# LEDSandButtons.net
KiCad netlist of a schematic drawn in Altium Designer
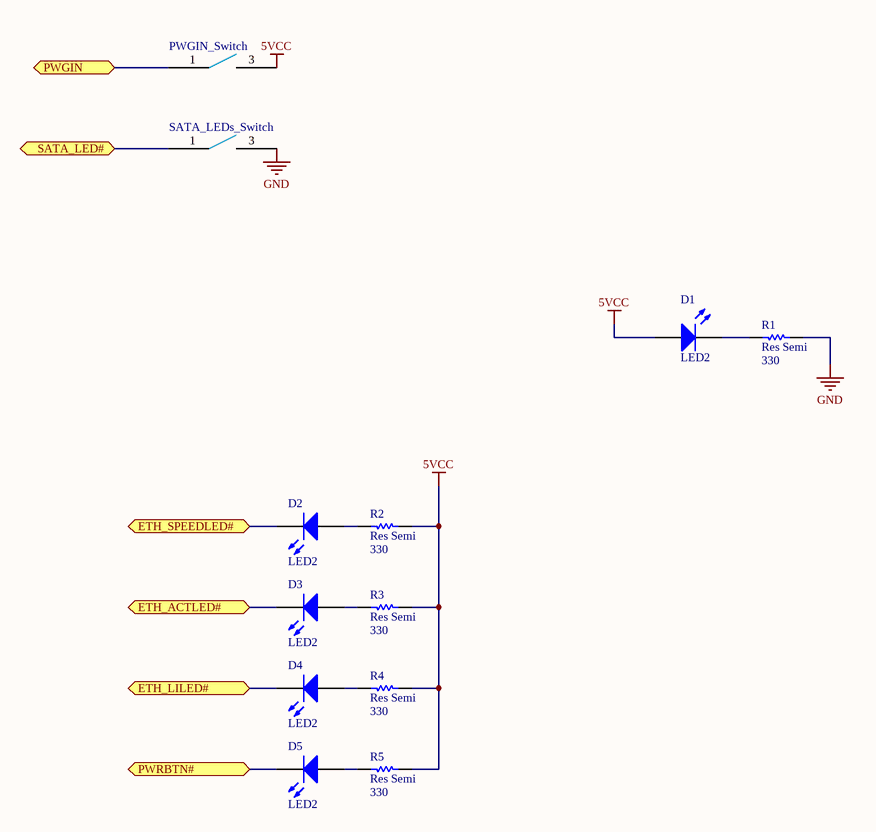
[diagram p0: LEDSandButtons.SchDoc]

(export (version "E")
  (design (tool "Eeschema 10.0.6"))
  (components
    (comp (ref "D1")
      (value "LED2")
      (footprint "C0805")
      (description "Typical RED, GREEN, YELLOW, AMBER GaAs LED")
      (fields (field (name "PUBLISHER") "Altium Limited"))
      (libsource (lib "Miscellaneous Devices") (part "LED2"))
    )
    (comp (ref "D2")
      (value "LED2")
      (footprint "C0805")
      (description "Typical RED, GREEN, YELLOW, AMBER GaAs LED")
      (fields (field (name "PUBLISHER") "Altium Limited"))
      (libsource (lib "Miscellaneous Devices") (part "LED2"))
    )
    (comp (ref "D3")
      (value "LED2")
      (footprint "C0805")
      (description "Typical RED, GREEN, YELLOW, AMBER GaAs LED")
      (fields (field (name "PUBLISHER") "Altium Limited"))
      (libsource (lib "Miscellaneous Devices") (part "LED2"))
    )
    (comp (ref "D4")
      (value "LED2")
      (footprint "C0805")
      (description "Typical RED, GREEN, YELLOW, AMBER GaAs LED")
      (fields (field (name "PUBLISHER") "Altium Limited"))
      (libsource (lib "Miscellaneous Devices") (part "LED2"))
    )
    (comp (ref "D5")
      (value "LED2")
      (footprint "C0805")
      (description "Typical RED, GREEN, YELLOW, AMBER GaAs LED")
      (fields (field (name "PUBLISHER") "Altium Limited"))
      (libsource (lib "Miscellaneous Devices") (part "LED2"))
    )
    (comp (ref "PWGIN_Switch")
      (value "Switch")
      (footprint "GS02MCBE")
      (libsource (lib "Buttons") (part "Switch"))
    )
    (comp (ref "R1")
      (value "Res Semi")
      (footprint "1005[0402]")
      (description "Semiconductor Resistor")
      (fields (field (name "ALTIUM_VALUE") "330") (field (name "PUBLISHER") "Altium Limited"))
      (libsource (lib "Miscellaneous Devices") (part "Res Semi"))
    )
    (comp (ref "R2")
      (value "Res Semi")
      (footprint "1005[0402]")
      (description "Semiconductor Resistor")
      (fields (field (name "ALTIUM_VALUE") "330") (field (name "PUBLISHER") "Altium Limited"))
      (libsource (lib "Miscellaneous Devices") (part "Res Semi"))
    )
    (comp (ref "R3")
      (value "Res Semi")
      (footprint "1005[0402]")
      (description "Semiconductor Resistor")
      (fields (field (name "ALTIUM_VALUE") "330") (field (name "PUBLISHER") "Altium Limited"))
      (libsource (lib "Miscellaneous Devices") (part "Res Semi"))
    )
    (comp (ref "R4")
      (value "Res Semi")
      (footprint "1005[0402]")
      (description "Semiconductor Resistor")
      (fields (field (name "ALTIUM_VALUE") "330") (field (name "PUBLISHER") "Altium Limited"))
      (libsource (lib "Miscellaneous Devices") (part "Res Semi"))
    )
    (comp (ref "R5")
      (value "Res Semi")
      (footprint "1005[0402]")
      (description "Semiconductor Resistor")
      (fields (field (name "ALTIUM_VALUE") "330") (field (name "PUBLISHER") "Altium Limited"))
      (libsource (lib "Miscellaneous Devices") (part "Res Semi"))
    )
    (comp (ref "SATA_LEDs_Switch")
      (value "Switch")
      (footprint "GS02MCBE")
      (libsource (lib "Buttons") (part "Switch"))
    )
  )
  (nets
    (net (code "1") (name "/ETH_ACTLED#") (class "Default")
      (node (ref "D3") (pin "2") (pinfunction "K_2") (pintype "passive"))
    )
    (net (code "2") (name "/ETH_LILED#") (class "Default")
      (node (ref "D4") (pin "2") (pinfunction "K_2") (pintype "passive"))
    )
    (net (code "3") (name "/ETH_SPEEDLED#") (class "Default")
      (node (ref "D2") (pin "2") (pinfunction "K_2") (pintype "passive"))
    )
    (net (code "4") (name "/PWGIN") (class "Default")
      (node (ref "PWGIN_Switch") (pin "1") (pinfunction "1_1") (pintype "passive"))
    )
    (net (code "5") (name "/PWRBTN#") (class "Default")
      (node (ref "D5") (pin "2") (pinfunction "K_2") (pintype "passive"))
    )
    (net (code "6") (name "/SATA_LED#") (class "Default")
      (node (ref "SATA_LEDs_Switch") (pin "1") (pinfunction "1_1") (pintype "passive"))
    )
    (net (code "7") (name "5VCC") (class "Default")
      (node (ref "D1") (pin "1") (pinfunction "A_1") (pintype "passive"))
      (node (ref "PWGIN_Switch") (pin "3") (pinfunction "3_3") (pintype "passive"))
      (node (ref "R2") (pin "1") (pinfunction "1_1") (pintype "passive"))
      (node (ref "R3") (pin "1") (pinfunction "1_1") (pintype "passive"))
      (node (ref "R4") (pin "1") (pinfunction "1_1") (pintype "passive"))
      (node (ref "R5") (pin "1") (pinfunction "1_1") (pintype "passive"))
    )
    (net (code "8") (name "GND") (class "Default")
      (node (ref "R1") (pin "1") (pinfunction "1_1") (pintype "passive"))
      (node (ref "SATA_LEDs_Switch") (pin "3") (pinfunction "3_3") (pintype "passive"))
    )
    (net (code "9") (name "Net-(D1-K)") (class "Default")
      (node (ref "D1") (pin "2") (pinfunction "K_2") (pintype "passive"))
      (node (ref "R1") (pin "2") (pinfunction "2_2") (pintype "passive"))
    )
    (net (code "10") (name "Net-(D2-A)") (class "Default")
      (node (ref "D2") (pin "1") (pinfunction "A_1") (pintype "passive"))
      (node (ref "R2") (pin "2") (pinfunction "2_2") (pintype "passive"))
    )
    (net (code "11") (name "Net-(D3-A)") (class "Default")
      (node (ref "D3") (pin "1") (pinfunction "A_1") (pintype "passive"))
      (node (ref "R3") (pin "2") (pinfunction "2_2") (pintype "passive"))
    )
    (net (code "12") (name "Net-(D4-A)") (class "Default")
      (node (ref "D4") (pin "1") (pinfunction "A_1") (pintype "passive"))
      (node (ref "R4") (pin "2") (pinfunction "2_2") (pintype "passive"))
    )
    (net (code "13") (name "Net-(D5-A)") (class "Default")
      (node (ref "D5") (pin "1") (pinfunction "A_1") (pintype "passive"))
      (node (ref "R5") (pin "2") (pinfunction "2_2") (pintype "passive"))
    )
  )
)
